# cubetto_1.net
KiCad netlist of a schematic drawn in EAGLE
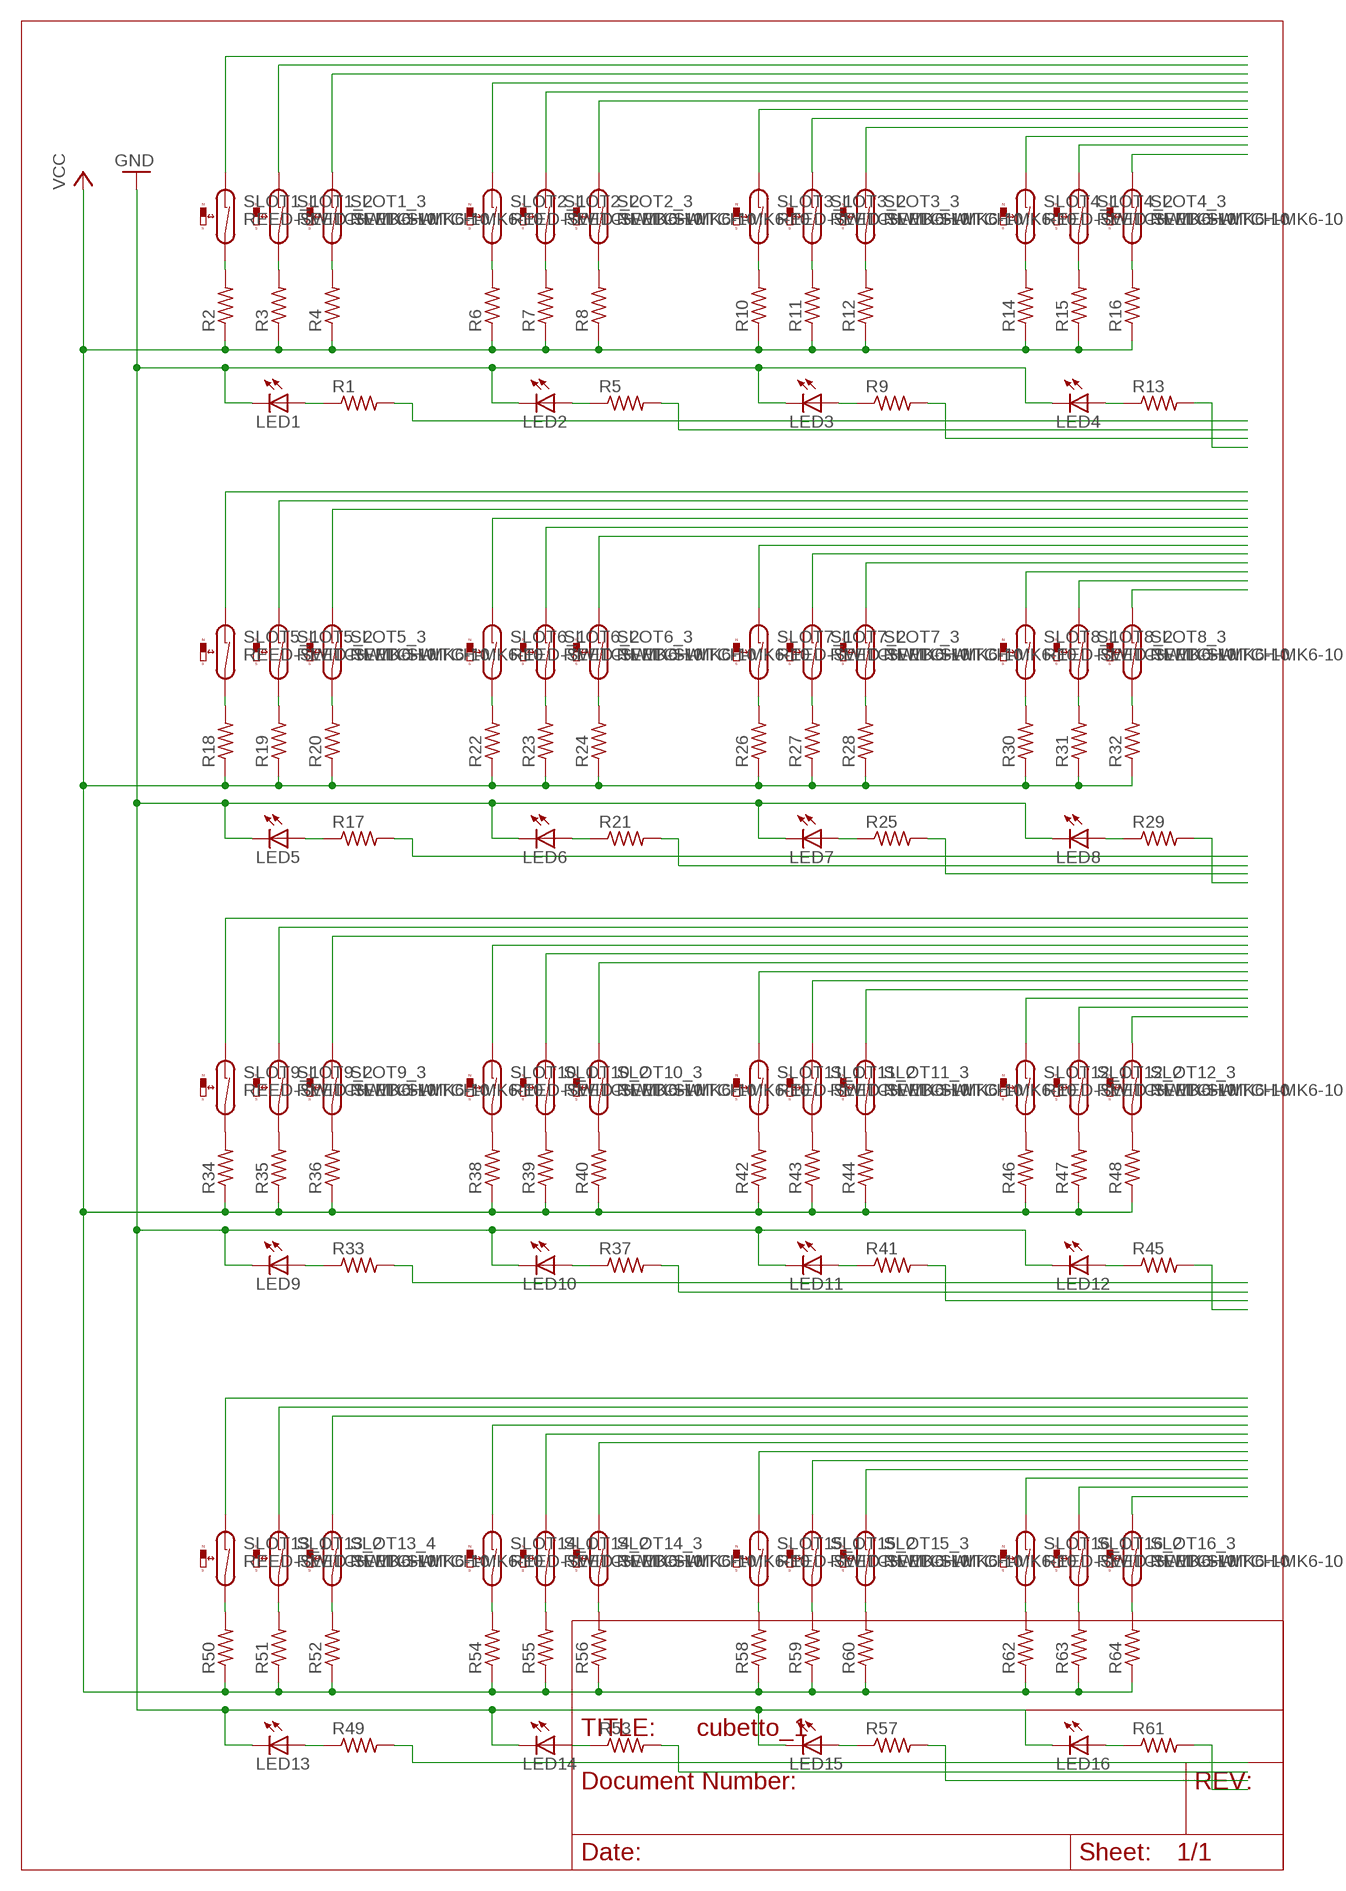
[diagram p0: schematic, sheet 1]

(export (version "E")
  (design (tool "Eeschema 10.0.6"))
  (components
    (comp (ref "LED1")
      (value "LED3MM")
      (footprint "eagle-import:LED3MM")
      (libsource (lib "eagle-import") (part "LED3MM"))
    )
    (comp (ref "LED2")
      (value "LED3MM")
      (footprint "eagle-import:LED3MM")
      (libsource (lib "eagle-import") (part "LED3MM"))
    )
    (comp (ref "LED3")
      (value "LED3MM")
      (footprint "eagle-import:LED3MM")
      (libsource (lib "eagle-import") (part "LED3MM"))
    )
    (comp (ref "LED4")
      (value "LED3MM")
      (footprint "eagle-import:LED3MM")
      (libsource (lib "eagle-import") (part "LED3MM"))
    )
    (comp (ref "LED5")
      (value "LED3MM")
      (footprint "eagle-import:LED3MM")
      (libsource (lib "eagle-import") (part "LED3MM"))
    )
    (comp (ref "LED6")
      (value "LED3MM")
      (footprint "eagle-import:LED3MM")
      (libsource (lib "eagle-import") (part "LED3MM"))
    )
    (comp (ref "LED7")
      (value "LED3MM")
      (footprint "eagle-import:LED3MM")
      (libsource (lib "eagle-import") (part "LED3MM"))
    )
    (comp (ref "LED8")
      (value "LED3MM")
      (footprint "eagle-import:LED3MM")
      (libsource (lib "eagle-import") (part "LED3MM"))
    )
    (comp (ref "LED9")
      (value "LED3MM")
      (footprint "eagle-import:LED3MM")
      (libsource (lib "eagle-import") (part "LED3MM"))
    )
    (comp (ref "LED10")
      (value "LED3MM")
      (footprint "eagle-import:LED3MM")
      (libsource (lib "eagle-import") (part "LED3MM"))
    )
    (comp (ref "LED11")
      (value "LED3MM")
      (footprint "eagle-import:LED3MM")
      (libsource (lib "eagle-import") (part "LED3MM"))
    )
    (comp (ref "LED12")
      (value "LED3MM")
      (footprint "eagle-import:LED3MM")
      (libsource (lib "eagle-import") (part "LED3MM"))
    )
    (comp (ref "LED13")
      (value "LED3MM")
      (footprint "eagle-import:LED3MM")
      (libsource (lib "eagle-import") (part "LED3MM"))
    )
    (comp (ref "LED14")
      (value "LED3MM")
      (footprint "eagle-import:LED3MM")
      (libsource (lib "eagle-import") (part "LED3MM"))
    )
    (comp (ref "LED15")
      (value "LED3MM")
      (footprint "eagle-import:LED3MM")
      (libsource (lib "eagle-import") (part "LED3MM"))
    )
    (comp (ref "LED16")
      (value "LED3MM")
      (footprint "eagle-import:LED3MM")
      (libsource (lib "eagle-import") (part "LED3MM"))
    )
    (comp (ref "R1")
      (value "R-US_0207/10")
      (footprint "eagle-import:0207_10")
      (libsource (lib "eagle-import") (part "R-US_0207/10"))
    )
    (comp (ref "R2")
      (value "R-US_0207/10")
      (footprint "eagle-import:0207_10")
      (libsource (lib "eagle-import") (part "R-US_0207/10"))
    )
    (comp (ref "R3")
      (value "R-US_0207/10")
      (footprint "eagle-import:0207_10")
      (libsource (lib "eagle-import") (part "R-US_0207/10"))
    )
    (comp (ref "R4")
      (value "R-US_0207/10")
      (footprint "eagle-import:0207_10")
      (libsource (lib "eagle-import") (part "R-US_0207/10"))
    )
    (comp (ref "R5")
      (value "R-US_0207/10")
      (footprint "eagle-import:0207_10")
      (libsource (lib "eagle-import") (part "R-US_0207/10"))
    )
    (comp (ref "R6")
      (value "R-US_0207/10")
      (footprint "eagle-import:0207_10")
      (libsource (lib "eagle-import") (part "R-US_0207/10"))
    )
    (comp (ref "R7")
      (value "R-US_0207/10")
      (footprint "eagle-import:0207_10")
      (libsource (lib "eagle-import") (part "R-US_0207/10"))
    )
    (comp (ref "R8")
      (value "R-US_0207/10")
      (footprint "eagle-import:0207_10")
      (libsource (lib "eagle-import") (part "R-US_0207/10"))
    )
    (comp (ref "R9")
      (value "R-US_0207/10")
      (footprint "eagle-import:0207_10")
      (libsource (lib "eagle-import") (part "R-US_0207/10"))
    )
    (comp (ref "R10")
      (value "R-US_0207/10")
      (footprint "eagle-import:0207_10")
      (libsource (lib "eagle-import") (part "R-US_0207/10"))
    )
    (comp (ref "R11")
      (value "R-US_0207/10")
      (footprint "eagle-import:0207_10")
      (libsource (lib "eagle-import") (part "R-US_0207/10"))
    )
    (comp (ref "R12")
      (value "R-US_0207/10")
      (footprint "eagle-import:0207_10")
      (libsource (lib "eagle-import") (part "R-US_0207/10"))
    )
    (comp (ref "R13")
      (value "R-US_0207/10")
      (footprint "eagle-import:0207_10")
      (libsource (lib "eagle-import") (part "R-US_0207/10"))
    )
    (comp (ref "R14")
      (value "R-US_0207/10")
      (footprint "eagle-import:0207_10")
      (libsource (lib "eagle-import") (part "R-US_0207/10"))
    )
    (comp (ref "R15")
      (value "R-US_0207/10")
      (footprint "eagle-import:0207_10")
      (libsource (lib "eagle-import") (part "R-US_0207/10"))
    )
    (comp (ref "R16")
      (value "R-US_0207/10")
      (footprint "eagle-import:0207_10")
      (libsource (lib "eagle-import") (part "R-US_0207/10"))
    )
    (comp (ref "R17")
      (value "R-US_0207/10")
      (footprint "eagle-import:0207_10")
      (libsource (lib "eagle-import") (part "R-US_0207/10"))
    )
    (comp (ref "R18")
      (value "R-US_0207/10")
      (footprint "eagle-import:0207_10")
      (libsource (lib "eagle-import") (part "R-US_0207/10"))
    )
    (comp (ref "R19")
      (value "R-US_0207/10")
      (footprint "eagle-import:0207_10")
      (libsource (lib "eagle-import") (part "R-US_0207/10"))
    )
    (comp (ref "R20")
      (value "R-US_0207/10")
      (footprint "eagle-import:0207_10")
      (libsource (lib "eagle-import") (part "R-US_0207/10"))
    )
    (comp (ref "R21")
      (value "R-US_0207/10")
      (footprint "eagle-import:0207_10")
      (libsource (lib "eagle-import") (part "R-US_0207/10"))
    )
    (comp (ref "R22")
      (value "R-US_0207/10")
      (footprint "eagle-import:0207_10")
      (libsource (lib "eagle-import") (part "R-US_0207/10"))
    )
    (comp (ref "R23")
      (value "R-US_0207/10")
      (footprint "eagle-import:0207_10")
      (libsource (lib "eagle-import") (part "R-US_0207/10"))
    )
    (comp (ref "R24")
      (value "R-US_0207/10")
      (footprint "eagle-import:0207_10")
      (libsource (lib "eagle-import") (part "R-US_0207/10"))
    )
    (comp (ref "R25")
      (value "R-US_0207/10")
      (footprint "eagle-import:0207_10")
      (libsource (lib "eagle-import") (part "R-US_0207/10"))
    )
    (comp (ref "R26")
      (value "R-US_0207/10")
      (footprint "eagle-import:0207_10")
      (libsource (lib "eagle-import") (part "R-US_0207/10"))
    )
    (comp (ref "R27")
      (value "R-US_0207/10")
      (footprint "eagle-import:0207_10")
      (libsource (lib "eagle-import") (part "R-US_0207/10"))
    )
    (comp (ref "R28")
      (value "R-US_0207/10")
      (footprint "eagle-import:0207_10")
      (libsource (lib "eagle-import") (part "R-US_0207/10"))
    )
    (comp (ref "R29")
      (value "R-US_0207/10")
      (footprint "eagle-import:0207_10")
      (libsource (lib "eagle-import") (part "R-US_0207/10"))
    )
    (comp (ref "R30")
      (value "R-US_0207/10")
      (footprint "eagle-import:0207_10")
      (libsource (lib "eagle-import") (part "R-US_0207/10"))
    )
    (comp (ref "R31")
      (value "R-US_0207/10")
      (footprint "eagle-import:0207_10")
      (libsource (lib "eagle-import") (part "R-US_0207/10"))
    )
    (comp (ref "R32")
      (value "R-US_0207/10")
      (footprint "eagle-import:0207_10")
      (libsource (lib "eagle-import") (part "R-US_0207/10"))
    )
    (comp (ref "R33")
      (value "R-US_0207/10")
      (footprint "eagle-import:0207_10")
      (libsource (lib "eagle-import") (part "R-US_0207/10"))
    )
    (comp (ref "R34")
      (value "R-US_0207/10")
      (footprint "eagle-import:0207_10")
      (libsource (lib "eagle-import") (part "R-US_0207/10"))
    )
    (comp (ref "R35")
      (value "R-US_0207/10")
      (footprint "eagle-import:0207_10")
      (libsource (lib "eagle-import") (part "R-US_0207/10"))
    )
    (comp (ref "R36")
      (value "R-US_0207/10")
      (footprint "eagle-import:0207_10")
      (libsource (lib "eagle-import") (part "R-US_0207/10"))
    )
    (comp (ref "R37")
      (value "R-US_0207/10")
      (footprint "eagle-import:0207_10")
      (libsource (lib "eagle-import") (part "R-US_0207/10"))
    )
    (comp (ref "R38")
      (value "R-US_0207/10")
      (footprint "eagle-import:0207_10")
      (libsource (lib "eagle-import") (part "R-US_0207/10"))
    )
    (comp (ref "R39")
      (value "R-US_0207/10")
      (footprint "eagle-import:0207_10")
      (libsource (lib "eagle-import") (part "R-US_0207/10"))
    )
    (comp (ref "R40")
      (value "R-US_0207/10")
      (footprint "eagle-import:0207_10")
      (libsource (lib "eagle-import") (part "R-US_0207/10"))
    )
    (comp (ref "R41")
      (value "R-US_0207/10")
      (footprint "eagle-import:0207_10")
      (libsource (lib "eagle-import") (part "R-US_0207/10"))
    )
    (comp (ref "R42")
      (value "R-US_0207/10")
      (footprint "eagle-import:0207_10")
      (libsource (lib "eagle-import") (part "R-US_0207/10"))
    )
    (comp (ref "R43")
      (value "R-US_0207/10")
      (footprint "eagle-import:0207_10")
      (libsource (lib "eagle-import") (part "R-US_0207/10"))
    )
    (comp (ref "R44")
      (value "R-US_0207/10")
      (footprint "eagle-import:0207_10")
      (libsource (lib "eagle-import") (part "R-US_0207/10"))
    )
    (comp (ref "R45")
      (value "R-US_0207/10")
      (footprint "eagle-import:0207_10")
      (libsource (lib "eagle-import") (part "R-US_0207/10"))
    )
    (comp (ref "R46")
      (value "R-US_0207/10")
      (footprint "eagle-import:0207_10")
      (libsource (lib "eagle-import") (part "R-US_0207/10"))
    )
    (comp (ref "R47")
      (value "R-US_0207/10")
      (footprint "eagle-import:0207_10")
      (libsource (lib "eagle-import") (part "R-US_0207/10"))
    )
    (comp (ref "R48")
      (value "R-US_0207/10")
      (footprint "eagle-import:0207_10")
      (libsource (lib "eagle-import") (part "R-US_0207/10"))
    )
    (comp (ref "R49")
      (value "R-US_0207/10")
      (footprint "eagle-import:0207_10")
      (libsource (lib "eagle-import") (part "R-US_0207/10"))
    )
    (comp (ref "R50")
      (value "R-US_0207/10")
      (footprint "eagle-import:0207_10")
      (libsource (lib "eagle-import") (part "R-US_0207/10"))
    )
    (comp (ref "R51")
      (value "R-US_0207/10")
      (footprint "eagle-import:0207_10")
      (libsource (lib "eagle-import") (part "R-US_0207/10"))
    )
    (comp (ref "R52")
      (value "R-US_0207/10")
      (footprint "eagle-import:0207_10")
      (libsource (lib "eagle-import") (part "R-US_0207/10"))
    )
    (comp (ref "R53")
      (value "R-US_0207/10")
      (footprint "eagle-import:0207_10")
      (libsource (lib "eagle-import") (part "R-US_0207/10"))
    )
    (comp (ref "R54")
      (value "R-US_0207/10")
      (footprint "eagle-import:0207_10")
      (libsource (lib "eagle-import") (part "R-US_0207/10"))
    )
    (comp (ref "R55")
      (value "R-US_0207/10")
      (footprint "eagle-import:0207_10")
      (libsource (lib "eagle-import") (part "R-US_0207/10"))
    )
    (comp (ref "R56")
      (value "R-US_0207/10")
      (footprint "eagle-import:0207_10")
      (libsource (lib "eagle-import") (part "R-US_0207/10"))
    )
    (comp (ref "R57")
      (value "R-US_0207/10")
      (footprint "eagle-import:0207_10")
      (libsource (lib "eagle-import") (part "R-US_0207/10"))
    )
    (comp (ref "R58")
      (value "R-US_0207/10")
      (footprint "eagle-import:0207_10")
      (libsource (lib "eagle-import") (part "R-US_0207/10"))
    )
    (comp (ref "R59")
      (value "R-US_0207/10")
      (footprint "eagle-import:0207_10")
      (libsource (lib "eagle-import") (part "R-US_0207/10"))
    )
    (comp (ref "R60")
      (value "R-US_0207/10")
      (footprint "eagle-import:0207_10")
      (libsource (lib "eagle-import") (part "R-US_0207/10"))
    )
    (comp (ref "R61")
      (value "R-US_0207/10")
      (footprint "eagle-import:0207_10")
      (libsource (lib "eagle-import") (part "R-US_0207/10"))
    )
    (comp (ref "R62")
      (value "R-US_0207/10")
      (footprint "eagle-import:0207_10")
      (libsource (lib "eagle-import") (part "R-US_0207/10"))
    )
    (comp (ref "R63")
      (value "R-US_0207/10")
      (footprint "eagle-import:0207_10")
      (libsource (lib "eagle-import") (part "R-US_0207/10"))
    )
    (comp (ref "R64")
      (value "R-US_0207/10")
      (footprint "eagle-import:0207_10")
      (libsource (lib "eagle-import") (part "R-US_0207/10"))
    )
    (comp (ref "SLOT1_1")
      (value "REED-SWITCH-MK6-10")
      (footprint "eagle-import:MK6-10")
      (libsource (lib "eagle-import") (part "REED-SWITCH-MK6-10"))
    )
    (comp (ref "SLOT1_2")
      (value "REED-SWITCH-MK6-10")
      (footprint "eagle-import:MK6-10")
      (libsource (lib "eagle-import") (part "REED-SWITCH-MK6-10"))
    )
    (comp (ref "SLOT1_3")
      (value "REED-SWITCH-MK6-10")
      (footprint "eagle-import:MK6-10")
      (libsource (lib "eagle-import") (part "REED-SWITCH-MK6-10"))
    )
    (comp (ref "SLOT2_1")
      (value "REED-SWITCH-MK6-10")
      (footprint "eagle-import:MK6-10")
      (libsource (lib "eagle-import") (part "REED-SWITCH-MK6-10"))
    )
    (comp (ref "SLOT2_2")
      (value "REED-SWITCH-MK6-10")
      (footprint "eagle-import:MK6-10")
      (libsource (lib "eagle-import") (part "REED-SWITCH-MK6-10"))
    )
    (comp (ref "SLOT2_3")
      (value "REED-SWITCH-MK6-10")
      (footprint "eagle-import:MK6-10")
      (libsource (lib "eagle-import") (part "REED-SWITCH-MK6-10"))
    )
    (comp (ref "SLOT3_1")
      (value "REED-SWITCH-MK6-10")
      (footprint "eagle-import:MK6-10")
      (libsource (lib "eagle-import") (part "REED-SWITCH-MK6-10"))
    )
    (comp (ref "SLOT3_2")
      (value "REED-SWITCH-MK6-10")
      (footprint "eagle-import:MK6-10")
      (libsource (lib "eagle-import") (part "REED-SWITCH-MK6-10"))
    )
    (comp (ref "SLOT3_3")
      (value "REED-SWITCH-MK6-10")
      (footprint "eagle-import:MK6-10")
      (libsource (lib "eagle-import") (part "REED-SWITCH-MK6-10"))
    )
    (comp (ref "SLOT4_1")
      (value "REED-SWITCH-MK6-10")
      (footprint "eagle-import:MK6-10")
      (libsource (lib "eagle-import") (part "REED-SWITCH-MK6-10"))
    )
    (comp (ref "SLOT4_2")
      (value "REED-SWITCH-MK6-10")
      (footprint "eagle-import:MK6-10")
      (libsource (lib "eagle-import") (part "REED-SWITCH-MK6-10"))
    )
    (comp (ref "SLOT4_3")
      (value "REED-SWITCH-MK6-10")
      (footprint "eagle-import:MK6-10")
      (libsource (lib "eagle-import") (part "REED-SWITCH-MK6-10"))
    )
    (comp (ref "SLOT5_1")
      (value "REED-SWITCH-MK6-10")
      (footprint "eagle-import:MK6-10")
      (libsource (lib "eagle-import") (part "REED-SWITCH-MK6-10"))
    )
    (comp (ref "SLOT5_2")
      (value "REED-SWITCH-MK6-10")
      (footprint "eagle-import:MK6-10")
      (libsource (lib "eagle-import") (part "REED-SWITCH-MK6-10"))
    )
    (comp (ref "SLOT5_3")
      (value "REED-SWITCH-MK6-10")
      (footprint "eagle-import:MK6-10")
      (libsource (lib "eagle-import") (part "REED-SWITCH-MK6-10"))
    )
    (comp (ref "SLOT6_1")
      (value "REED-SWITCH-MK6-10")
      (footprint "eagle-import:MK6-10")
      (libsource (lib "eagle-import") (part "REED-SWITCH-MK6-10"))
    )
    (comp (ref "SLOT6_2")
      (value "REED-SWITCH-MK6-10")
      (footprint "eagle-import:MK6-10")
      (libsource (lib "eagle-import") (part "REED-SWITCH-MK6-10"))
    )
    (comp (ref "SLOT6_3")
      (value "REED-SWITCH-MK6-10")
      (footprint "eagle-import:MK6-10")
      (libsource (lib "eagle-import") (part "REED-SWITCH-MK6-10"))
    )
    (comp (ref "SLOT7_1")
      (value "REED-SWITCH-MK6-10")
      (footprint "eagle-import:MK6-10")
      (libsource (lib "eagle-import") (part "REED-SWITCH-MK6-10"))
    )
    (comp (ref "SLOT7_2")
      (value "REED-SWITCH-MK6-10")
      (footprint "eagle-import:MK6-10")
      (libsource (lib "eagle-import") (part "REED-SWITCH-MK6-10"))
    )
    (comp (ref "SLOT7_3")
      (value "REED-SWITCH-MK6-10")
      (footprint "eagle-import:MK6-10")
      (libsource (lib "eagle-import") (part "REED-SWITCH-MK6-10"))
    )
    (comp (ref "SLOT8_1")
      (value "REED-SWITCH-MK6-10")
      (footprint "eagle-import:MK6-10")
      (libsource (lib "eagle-import") (part "REED-SWITCH-MK6-10"))
    )
    (comp (ref "SLOT8_2")
      (value "REED-SWITCH-MK6-10")
      (footprint "eagle-import:MK6-10")
      (libsource (lib "eagle-import") (part "REED-SWITCH-MK6-10"))
    )
    (comp (ref "SLOT8_3")
      (value "REED-SWITCH-MK6-10")
      (footprint "eagle-import:MK6-10")
      (libsource (lib "eagle-import") (part "REED-SWITCH-MK6-10"))
    )
    (comp (ref "SLOT9_1")
      (value "REED-SWITCH-MK6-10")
      (footprint "eagle-import:MK6-10")
      (libsource (lib "eagle-import") (part "REED-SWITCH-MK6-10"))
    )
    (comp (ref "SLOT9_2")
      (value "REED-SWITCH-MK6-10")
      (footprint "eagle-import:MK6-10")
      (libsource (lib "eagle-import") (part "REED-SWITCH-MK6-10"))
    )
    (comp (ref "SLOT9_3")
      (value "REED-SWITCH-MK6-10")
      (footprint "eagle-import:MK6-10")
      (libsource (lib "eagle-import") (part "REED-SWITCH-MK6-10"))
    )
    (comp (ref "SLOT10_1")
      (value "REED-SWITCH-MK6-10")
      (footprint "eagle-import:MK6-10")
      (libsource (lib "eagle-import") (part "REED-SWITCH-MK6-10"))
    )
    (comp (ref "SLOT10_2")
      (value "REED-SWITCH-MK6-10")
      (footprint "eagle-import:MK6-10")
      (libsource (lib "eagle-import") (part "REED-SWITCH-MK6-10"))
    )
    (comp (ref "SLOT10_3")
      (value "REED-SWITCH-MK6-10")
      (footprint "eagle-import:MK6-10")
      (libsource (lib "eagle-import") (part "REED-SWITCH-MK6-10"))
    )
    (comp (ref "SLOT11_1")
      (value "REED-SWITCH-MK6-10")
      (footprint "eagle-import:MK6-10")
      (libsource (lib "eagle-import") (part "REED-SWITCH-MK6-10"))
    )
    (comp (ref "SLOT11_2")
      (value "REED-SWITCH-MK6-10")
      (footprint "eagle-import:MK6-10")
      (libsource (lib "eagle-import") (part "REED-SWITCH-MK6-10"))
    )
    (comp (ref "SLOT11_3")
      (value "REED-SWITCH-MK6-10")
      (footprint "eagle-import:MK6-10")
      (libsource (lib "eagle-import") (part "REED-SWITCH-MK6-10"))
    )
    (comp (ref "SLOT12_1")
      (value "REED-SWITCH-MK6-10")
      (footprint "eagle-import:MK6-10")
      (libsource (lib "eagle-import") (part "REED-SWITCH-MK6-10"))
    )
    (comp (ref "SLOT12_2")
      (value "REED-SWITCH-MK6-10")
      (footprint "eagle-import:MK6-10")
      (libsource (lib "eagle-import") (part "REED-SWITCH-MK6-10"))
    )
    (comp (ref "SLOT12_3")
      (value "REED-SWITCH-MK6-10")
      (footprint "eagle-import:MK6-10")
      (libsource (lib "eagle-import") (part "REED-SWITCH-MK6-10"))
    )
    (comp (ref "SLOT13_1")
      (value "REED-SWITCH-MK6-10")
      (footprint "eagle-import:MK6-10")
      (libsource (lib "eagle-import") (part "REED-SWITCH-MK6-10"))
    )
    (comp (ref "SLOT13_2")
      (value "REED-SWITCH-MK6-10")
      (footprint "eagle-import:MK6-10")
      (libsource (lib "eagle-import") (part "REED-SWITCH-MK6-10"))
    )
    (comp (ref "SLOT13_4")
      (value "REED-SWITCH-MK6-10")
      (footprint "eagle-import:MK6-10")
      (libsource (lib "eagle-import") (part "REED-SWITCH-MK6-10"))
    )
    (comp (ref "SLOT14_1")
      (value "REED-SWITCH-MK6-10")
      (footprint "eagle-import:MK6-10")
      (libsource (lib "eagle-import") (part "REED-SWITCH-MK6-10"))
    )
    (comp (ref "SLOT14_2")
      (value "REED-SWITCH-MK6-10")
      (footprint "eagle-import:MK6-10")
      (libsource (lib "eagle-import") (part "REED-SWITCH-MK6-10"))
    )
    (comp (ref "SLOT14_3")
      (value "REED-SWITCH-MK6-10")
      (footprint "eagle-import:MK6-10")
      (libsource (lib "eagle-import") (part "REED-SWITCH-MK6-10"))
    )
    (comp (ref "SLOT15_1")
      (value "REED-SWITCH-MK6-10")
      (footprint "eagle-import:MK6-10")
      (libsource (lib "eagle-import") (part "REED-SWITCH-MK6-10"))
    )
    (comp (ref "SLOT15_2")
      (value "REED-SWITCH-MK6-10")
      (footprint "eagle-import:MK6-10")
      (libsource (lib "eagle-import") (part "REED-SWITCH-MK6-10"))
    )
    (comp (ref "SLOT15_3")
      (value "REED-SWITCH-MK6-10")
      (footprint "eagle-import:MK6-10")
      (libsource (lib "eagle-import") (part "REED-SWITCH-MK6-10"))
    )
    (comp (ref "SLOT16_1")
      (value "REED-SWITCH-MK6-10")
      (footprint "eagle-import:MK6-10")
      (libsource (lib "eagle-import") (part "REED-SWITCH-MK6-10"))
    )
    (comp (ref "SLOT16_2")
      (value "REED-SWITCH-MK6-10")
      (footprint "eagle-import:MK6-10")
      (libsource (lib "eagle-import") (part "REED-SWITCH-MK6-10"))
    )
    (comp (ref "SLOT16_3")
      (value "REED-SWITCH-MK6-10")
      (footprint "eagle-import:MK6-10")
      (libsource (lib "eagle-import") (part "REED-SWITCH-MK6-10"))
    )
  )
  (nets
    (net (code "1") (name "GND") (class "Default")
      (node (ref "LED1") (pin "K") (pinfunction "C_K") (pintype "passive"))
      (node (ref "LED10") (pin "K") (pinfunction "C_K") (pintype "passive"))
      (node (ref "LED11") (pin "K") (pinfunction "C_K") (pintype "passive"))
      (node (ref "LED12") (pin "K") (pinfunction "C_K") (pintype "passive"))
      (node (ref "LED13") (pin "K") (pinfunction "C_K") (pintype "passive"))
      (node (ref "LED14") (pin "K") (pinfunction "C_K") (pintype "passive"))
      (node (ref "LED15") (pin "K") (pinfunction "C_K") (pintype "passive"))
      (node (ref "LED16") (pin "K") (pinfunction "C_K") (pintype "passive"))
      (node (ref "LED2") (pin "K") (pinfunction "C_K") (pintype "passive"))
      (node (ref "LED3") (pin "K") (pinfunction "C_K") (pintype "passive"))
      (node (ref "LED4") (pin "K") (pinfunction "C_K") (pintype "passive"))
      (node (ref "LED5") (pin "K") (pinfunction "C_K") (pintype "passive"))
      (node (ref "LED6") (pin "K") (pinfunction "C_K") (pintype "passive"))
      (node (ref "LED7") (pin "K") (pinfunction "C_K") (pintype "passive"))
      (node (ref "LED8") (pin "K") (pinfunction "C_K") (pintype "passive"))
      (node (ref "LED9") (pin "K") (pinfunction "C_K") (pintype "passive"))
    )
    (net (code "2") (name "Net-(LED1-PadA)") (class "Default")
      (node (ref "LED1") (pin "A") (pinfunction "A_A") (pintype "passive"))
      (node (ref "R1") (pin "1") (pinfunction "1_1") (pintype "passive"))
    )
    (net (code "3") (name "Net-(LED2-PadA)") (class "Default")
      (node (ref "LED2") (pin "A") (pinfunction "A_A") (pintype "passive"))
      (node (ref "R5") (pin "1") (pinfunction "1_1") (pintype "passive"))
    )
    (net (code "4") (name "Net-(LED3-PadA)") (class "Default")
      (node (ref "LED3") (pin "A") (pinfunction "A_A") (pintype "passive"))
      (node (ref "R9") (pin "1") (pinfunction "1_1") (pintype "passive"))
    )
    (net (code "5") (name "Net-(LED4-PadA)") (class "Default")
      (node (ref "LED4") (pin "A") (pinfunction "A_A") (pintype "passive"))
      (node (ref "R13") (pin "1") (pinfunction "1_1") (pintype "passive"))
    )
    (net (code "6") (name "Net-(LED5-PadA)") (class "Default")
      (node (ref "LED5") (pin "A") (pinfunction "A_A") (pintype "passive"))
      (node (ref "R17") (pin "1") (pinfunction "1_1") (pintype "passive"))
    )
    (net (code "7") (name "Net-(LED6-PadA)") (class "Default")
      (node (ref "LED6") (pin "A") (pinfunction "A_A") (pintype "passive"))
      (node (ref "R21") (pin "1") (pinfunction "1_1") (pintype "passive"))
    )
    (net (code "8") (name "Net-(LED7-PadA)") (class "Default")
      (node (ref "LED7") (pin "A") (pinfunction "A_A") (pintype "passive"))
      (node (ref "R25") (pin "1") (pinfunction "1_1") (pintype "passive"))
    )
    (net (code "9") (name "Net-(LED8-PadA)") (class "Default")
      (node (ref "LED8") (pin "A") (pinfunction "A_A") (pintype "passive"))
      (node (ref "R29") (pin "1") (pinfunction "1_1") (pintype "passive"))
    )
    (net (code "10") (name "Net-(LED9-PadA)") (class "Default")
      (node (ref "LED9") (pin "A") (pinfunction "A_A") (pintype "passive"))
      (node (ref "R33") (pin "1") (pinfunction "1_1") (pintype "passive"))
    )
    (net (code "11") (name "Net-(LED10-PadA)") (class "Default")
      (node (ref "LED10") (pin "A") (pinfunction "A_A") (pintype "passive"))
      (node (ref "R37") (pin "1") (pinfunction "1_1") (pintype "passive"))
    )
    (net (code "12") (name "Net-(LED11-PadA)") (class "Default")
      (node (ref "LED11") (pin "A") (pinfunction "A_A") (pintype "passive"))
      (node (ref "R41") (pin "1") (pinfunction "1_1") (pintype "passive"))
    )
    (net (code "13") (name "Net-(LED12-PadA)") (class "Default")
      (node (ref "LED12") (pin "A") (pinfunction "A_A") (pintype "passive"))
      (node (ref "R45") (pin "1") (pinfunction "1_1") (pintype "passive"))
    )
    (net (code "14") (name "Net-(LED13-PadA)") (class "Default")
      (node (ref "LED13") (pin "A") (pinfunction "A_A") (pintype "passive"))
      (node (ref "R49") (pin "1") (pinfunction "1_1") (pintype "passive"))
    )
    (net (code "15") (name "Net-(LED14-PadA)") (class "Default")
      (node (ref "LED14") (pin "A") (pinfunction "A_A") (pintype "passive"))
      (node (ref "R53") (pin "1") (pinfunction "1_1") (pintype "passive"))
    )
    (net (code "16") (name "Net-(LED15-PadA)") (class "Default")
      (node (ref "LED15") (pin "A") (pinfunction "A_A") (pintype "passive"))
      (node (ref "R57") (pin "1") (pinfunction "1_1") (pintype "passive"))
    )
    (net (code "17") (name "Net-(LED16-PadA)") (class "Default")
      (node (ref "LED16") (pin "A") (pinfunction "A_A") (pintype "passive"))
      (node (ref "R61") (pin "1") (pinfunction "1_1") (pintype "passive"))
    )
    (net (code "18") (name "Net-(R2-Pad2)") (class "Default")
      (node (ref "R2") (pin "2") (pinfunction "2_2") (pintype "passive"))
      (node (ref "SLOT1_1") (pin "2") (pinfunction "2_2") (pintype "passive"))
    )
    (net (code "19") (name "Net-(R3-Pad2)") (class "Default")
      (node (ref "R3") (pin "2") (pinfunction "2_2") (pintype "passive"))
      (node (ref "SLOT1_2") (pin "2") (pinfunction "2_2") (pintype "passive"))
    )
    (net (code "20") (name "Net-(R4-Pad2)") (class "Default")
      (node (ref "R4") (pin "2") (pinfunction "2_2") (pintype "passive"))
      (node (ref "SLOT1_3") (pin "2") (pinfunction "2_2") (pintype "passive"))
    )
    (net (code "21") (name "Net-(R6-Pad2)") (class "Default")
      (node (ref "R6") (pin "2") (pinfunction "2_2") (pintype "passive"))
      (node (ref "SLOT2_1") (pin "2") (pinfunction "2_2") (pintype "passive"))
    )
    (net (code "22") (name "Net-(R7-Pad2)") (class "Default")
      (node (ref "R7") (pin "2") (pinfunction "2_2") (pintype "passive"))
      (node (ref "SLOT2_2") (pin "2") (pinfunction "2_2") (pintype "passive"))
    )
    (net (code "23") (name "Net-(R8-Pad2)") (class "Default")
      (node (ref "R8") (pin "2") (pinfunction "2_2") (pintype "passive"))
      (node (ref "SLOT2_3") (pin "2") (pinfunction "2_2") (pintype "passive"))
    )
    (net (code "24") (name "Net-(R10-Pad2)") (class "Default")
      (node (ref "R10") (pin "2") (pinfunction "2_2") (pintype "passive"))
      (node (ref "SLOT3_1") (pin "2") (pinfunction "2_2") (pintype "passive"))
    )
    (net (code "25") (name "Net-(R11-Pad2)") (class "Default")
      (node (ref "R11") (pin "2") (pinfunction "2_2") (pintype "passive"))
      (node (ref "SLOT3_2") (pin "2") (pinfunction "2_2") (pintype "passive"))
    )
    (net (code "26") (name "Net-(R12-Pad2)") (class "Default")
      (node (ref "R12") (pin "2") (pinfunction "2_2") (pintype "passive"))
      (node (ref "SLOT3_3") (pin "2") (pinfunction "2_2") (pintype "passive"))
    )
    (net (code "27") (name "Net-(R14-Pad2)") (class "Default")
      (node (ref "R14") (pin "2") (pinfunction "2_2") (pintype "passive"))
      (node (ref "SLOT4_1") (pin "2") (pinfunction "2_2") (pintype "passive"))
    )
    (net (code "28") (name "Net-(R15-Pad2)") (class "Default")
      (node (ref "R15") (pin "2") (pinfunction "2_2") (pintype "passive"))
      (node (ref "SLOT4_2") (pin "2") (pinfunction "2_2") (pintype "passive"))
    )
    (net (code "29") (name "Net-(R16-Pad2)") (class "Default")
      (node (ref "R16") (pin "2") (pinfunction "2_2") (pintype "passive"))
      (node (ref "SLOT4_3") (pin "2") (pinfunction "2_2") (pintype "passive"))
    )
    (net (code "30") (name "Net-(R18-Pad2)") (class "Default")
      (node (ref "R18") (pin "2") (pinfunction "2_2") (pintype "passive"))
      (node (ref "SLOT5_1") (pin "2") (pinfunction "2_2") (pintype "passive"))
    )
    (net (code "31") (name "Net-(R19-Pad2)") (class "Default")
      (node (ref "R19") (pin "2") (pinfunction "2_2") (pintype "passive"))
      (node (ref "SLOT5_2") (pin "2") (pinfunction "2_2") (pintype "passive"))
    )
    (net (code "32") (name "Net-(R20-Pad2)") (class "Default")
      (node (ref "R20") (pin "2") (pinfunction "2_2") (pintype "passive"))
      (node (ref "SLOT5_3") (pin "2") (pinfunction "2_2") (pintype "passive"))
    )
    (net (code "33") (name "Net-(R22-Pad2)") (class "Default")
      (node (ref "R22") (pin "2") (pinfunction "2_2") (pintype "passive"))
      (node (ref "SLOT6_1") (pin "2") (pinfunction "2_2") (pintype "passive"))
    )
    (net (code "34") (name "Net-(R23-Pad2)") (class "Default")
      (node (ref "R23") (pin "2") (pinfunction "2_2") (pintype "passive"))
      (node (ref "SLOT6_2") (pin "2") (pinfunction "2_2") (pintype "passive"))
    )
    (net (code "35") (name "Net-(R24-Pad2)") (class "Default")
      (node (ref "R24") (pin "2") (pinfunction "2_2") (pintype "passive"))
      (node (ref "SLOT6_3") (pin "2") (pinfunction "2_2") (pintype "passive"))
    )
    (net (code "36") (name "Net-(R26-Pad2)") (class "Default")
      (node (ref "R26") (pin "2") (pinfunction "2_2") (pintype "passive"))
      (node (ref "SLOT7_1") (pin "2") (pinfunction "2_2") (pintype "passive"))
    )
    (net (code "37") (name "Net-(R27-Pad2)") (class "Default")
      (node (ref "R27") (pin "2") (pinfunction "2_2") (pintype "passive"))
      (node (ref "SLOT7_2") (pin "2") (pinfunction "2_2") (pintype "passive"))
    )
    (net (code "38") (name "Net-(R28-Pad2)") (class "Default")
      (node (ref "R28") (pin "2") (pinfunction "2_2") (pintype "passive"))
      (node (ref "SLOT7_3") (pin "2") (pinfunction "2_2") (pintype "passive"))
    )
    (net (code "39") (name "Net-(R30-Pad2)") (class "Default")
      (node (ref "R30") (pin "2") (pinfunction "2_2") (pintype "passive"))
      (node (ref "SLOT8_1") (pin "2") (pinfunction "2_2") (pintype "passive"))
    )
    (net (code "40") (name "Net-(R31-Pad2)") (class "Default")
      (node (ref "R31") (pin "2") (pinfunction "2_2") (pintype "passive"))
      (node (ref "SLOT8_2") (pin "2") (pinfunction "2_2") (pintype "passive"))
    )
    (net (code "41") (name "Net-(R32-Pad2)") (class "Default")
      (node (ref "R32") (pin "2") (pinfunction "2_2") (pintype "passive"))
      (node (ref "SLOT8_3") (pin "2") (pinfunction "2_2") (pintype "passive"))
    )
    (net (code "42") (name "Net-(R34-Pad2)") (class "Default")
      (node (ref "R34") (pin "2") (pinfunction "2_2") (pintype "passive"))
      (node (ref "SLOT9_1") (pin "2") (pinfunction "2_2") (pintype "passive"))
    )
    (net (code "43") (name "Net-(R35-Pad2)") (class "Default")
      (node (ref "R35") (pin "2") (pinfunction "2_2") (pintype "passive"))
      (node (ref "SLOT9_2") (pin "2") (pinfunction "2_2") (pintype "passive"))
    )
    (net (code "44") (name "Net-(R36-Pad2)") (class "Default")
      (node (ref "R36") (pin "2") (pinfunction "2_2") (pintype "passive"))
      (node (ref "SLOT9_3") (pin "2") (pinfunction "2_2") (pintype "passive"))
    )
    (net (code "45") (name "Net-(R38-Pad2)") (class "Default")
      (node (ref "R38") (pin "2") (pinfunction "2_2") (pintype "passive"))
      (node (ref "SLOT10_1") (pin "2") (pinfunction "2_2") (pintype "passive"))
    )
    (net (code "46") (name "Net-(R39-Pad2)") (class "Default")
      (node (ref "R39") (pin "2") (pinfunction "2_2") (pintype "passive"))
      (node (ref "SLOT10_2") (pin "2") (pinfunction "2_2") (pintype "passive"))
    )
    (net (code "47") (name "Net-(R40-Pad2)") (class "Default")
      (node (ref "R40") (pin "2") (pinfunction "2_2") (pintype "passive"))
      (node (ref "SLOT10_3") (pin "2") (pinfunction "2_2") (pintype "passive"))
    )
    (net (code "48") (name "Net-(R42-Pad2)") (class "Default")
      (node (ref "R42") (pin "2") (pinfunction "2_2") (pintype "passive"))
      (node (ref "SLOT11_1") (pin "2") (pinfunction "2_2") (pintype "passive"))
    )
    (net (code "49") (name "Net-(R43-Pad2)") (class "Default")
      (node (ref "R43") (pin "2") (pinfunction "2_2") (pintype "passive"))
      (node (ref "SLOT11_2") (pin "2") (pinfunction "2_2") (pintype "passive"))
    )
    (net (code "50") (name "Net-(R44-Pad2)") (class "Default")
      (node (ref "R44") (pin "2") (pinfunction "2_2") (pintype "passive"))
      (node (ref "SLOT11_3") (pin "2") (pinfunction "2_2") (pintype "passive"))
    )
    (net (code "51") (name "Net-(R46-Pad2)") (class "Default")
      (node (ref "R46") (pin "2") (pinfunction "2_2") (pintype "passive"))
      (node (ref "SLOT12_1") (pin "2") (pinfunction "2_2") (pintype "passive"))
    )
    (net (code "52") (name "Net-(R47-Pad2)") (class "Default")
      (node (ref "R47") (pin "2") (pinfunction "2_2") (pintype "passive"))
      (node (ref "SLOT12_2") (pin "2") (pinfunction "2_2") (pintype "passive"))
    )
    (net (code "53") (name "Net-(R48-Pad2)") (class "Default")
      (node (ref "R48") (pin "2") (pinfunction "2_2") (pintype "passive"))
      (node (ref "SLOT12_3") (pin "2") (pinfunction "2_2") (pintype "passive"))
    )
    (net (code "54") (name "Net-(R50-Pad2)") (class "Default")
      (node (ref "R50") (pin "2") (pinfunction "2_2") (pintype "passive"))
      (node (ref "SLOT13_1") (pin "2") (pinfunction "2_2") (pintype "passive"))
    )
    (net (code "55") (name "Net-(R51-Pad2)") (class "Default")
      (node (ref "R51") (pin "2") (pinfunction "2_2") (pintype "passive"))
      (node (ref "SLOT13_2") (pin "2") (pinfunction "2_2") (pintype "passive"))
    )
    (net (code "56") (name "Net-(R52-Pad2)") (class "Default")
      (node (ref "R52") (pin "2") (pinfunction "2_2") (pintype "passive"))
      (node (ref "SLOT13_4") (pin "2") (pinfunction "2_2") (pintype "passive"))
    )
    (net (code "57") (name "Net-(R54-Pad2)") (class "Default")
      (node (ref "R54") (pin "2") (pinfunction "2_2") (pintype "passive"))
      (node (ref "SLOT14_1") (pin "2") (pinfunction "2_2") (pintype "passive"))
    )
    (net (code "58") (name "Net-(R55-Pad2)") (class "Default")
      (node (ref "R55") (pin "2") (pinfunction "2_2") (pintype "passive"))
      (node (ref "SLOT14_2") (pin "2") (pinfunction "2_2") (pintype "passive"))
    )
    (net (code "59") (name "Net-(R56-Pad2)") (class "Default")
      (node (ref "R56") (pin "2") (pinfunction "2_2") (pintype "passive"))
      (node (ref "SLOT14_3") (pin "2") (pinfunction "2_2") (pintype "passive"))
    )
    (net (code "60") (name "Net-(R58-Pad2)") (class "Default")
      (node (ref "R58") (pin "2") (pinfunction "2_2") (pintype "passive"))
      (node (ref "SLOT15_1") (pin "2") (pinfunction "2_2") (pintype "passive"))
    )
    (net (code "61") (name "Net-(R59-Pad2)") (class "Default")
      (node (ref "R59") (pin "2") (pinfunction "2_2") (pintype "passive"))
      (node (ref "SLOT15_2") (pin "2") (pinfunction "2_2") (pintype "passive"))
    )
    (net (code "62") (name "Net-(R60-Pad2)") (class "Default")
      (node (ref "R60") (pin "2") (pinfunction "2_2") (pintype "passive"))
      (node (ref "SLOT15_3") (pin "2") (pinfunction "2_2") (pintype "passive"))
    )
    (net (code "63") (name "Net-(R62-Pad2)") (class "Default")
      (node (ref "R62") (pin "2") (pinfunction "2_2") (pintype "passive"))
      (node (ref "SLOT16_1") (pin "2") (pinfunction "2_2") (pintype "passive"))
    )
    (net (code "64") (name "Net-(R63-Pad2)") (class "Default")
      (node (ref "R63") (pin "2") (pinfunction "2_2") (pintype "passive"))
      (node (ref "SLOT16_2") (pin "2") (pinfunction "2_2") (pintype "passive"))
    )
    (net (code "65") (name "Net-(R64-Pad2)") (class "Default")
      (node (ref "R64") (pin "2") (pinfunction "2_2") (pintype "passive"))
      (node (ref "SLOT16_3") (pin "2") (pinfunction "2_2") (pintype "passive"))
    )
    (net (code "66") (name "VCC") (class "Default")
      (node (ref "R10") (pin "1") (pinfunction "1_1") (pintype "passive"))
      (node (ref "R11") (pin "1") (pinfunction "1_1") (pintype "passive"))
      (node (ref "R12") (pin "1") (pinfunction "1_1") (pintype "passive"))
      (node (ref "R14") (pin "1") (pinfunction "1_1") (pintype "passive"))
      (node (ref "R15") (pin "1") (pinfunction "1_1") (pintype "passive"))
      (node (ref "R16") (pin "1") (pinfunction "1_1") (pintype "passive"))
      (node (ref "R18") (pin "1") (pinfunction "1_1") (pintype "passive"))
      (node (ref "R19") (pin "1") (pinfunction "1_1") (pintype "passive"))
      (node (ref "R2") (pin "1") (pinfunction "1_1") (pintype "passive"))
      (node (ref "R20") (pin "1") (pinfunction "1_1") (pintype "passive"))
      (node (ref "R22") (pin "1") (pinfunction "1_1") (pintype "passive"))
      (node (ref "R23") (pin "1") (pinfunction "1_1") (pintype "passive"))
      (node (ref "R24") (pin "1") (pinfunction "1_1") (pintype "passive"))
      (node (ref "R26") (pin "1") (pinfunction "1_1") (pintype "passive"))
      (node (ref "R27") (pin "1") (pinfunction "1_1") (pintype "passive"))
      (node (ref "R28") (pin "1") (pinfunction "1_1") (pintype "passive"))
      (node (ref "R3") (pin "1") (pinfunction "1_1") (pintype "passive"))
      (node (ref "R30") (pin "1") (pinfunction "1_1") (pintype "passive"))
      (node (ref "R31") (pin "1") (pinfunction "1_1") (pintype "passive"))
      (node (ref "R32") (pin "1") (pinfunction "1_1") (pintype "passive"))
      (node (ref "R34") (pin "1") (pinfunction "1_1") (pintype "passive"))
      (node (ref "R35") (pin "1") (pinfunction "1_1") (pintype "passive"))
      (node (ref "R36") (pin "1") (pinfunction "1_1") (pintype "passive"))
      (node (ref "R38") (pin "1") (pinfunction "1_1") (pintype "passive"))
      (node (ref "R39") (pin "1") (pinfunction "1_1") (pintype "passive"))
      (node (ref "R4") (pin "1") (pinfunction "1_1") (pintype "passive"))
      (node (ref "R40") (pin "1") (pinfunction "1_1") (pintype "passive"))
      (node (ref "R42") (pin "1") (pinfunction "1_1") (pintype "passive"))
      (node (ref "R43") (pin "1") (pinfunction "1_1") (pintype "passive"))
      (node (ref "R44") (pin "1") (pinfunction "1_1") (pintype "passive"))
      (node (ref "R46") (pin "1") (pinfunction "1_1") (pintype "passive"))
      (node (ref "R47") (pin "1") (pinfunction "1_1") (pintype "passive"))
      (node (ref "R48") (pin "1") (pinfunction "1_1") (pintype "passive"))
      (node (ref "R50") (pin "1") (pinfunction "1_1") (pintype "passive"))
      (node (ref "R51") (pin "1") (pinfunction "1_1") (pintype "passive"))
      (node (ref "R52") (pin "1") (pinfunction "1_1") (pintype "passive"))
      (node (ref "R54") (pin "1") (pinfunction "1_1") (pintype "passive"))
      (node (ref "R55") (pin "1") (pinfunction "1_1") (pintype "passive"))
      (node (ref "R56") (pin "1") (pinfunction "1_1") (pintype "passive"))
      (node (ref "R58") (pin "1") (pinfunction "1_1") (pintype "passive"))
      (node (ref "R59") (pin "1") (pinfunction "1_1") (pintype "passive"))
      (node (ref "R6") (pin "1") (pinfunction "1_1") (pintype "passive"))
      (node (ref "R60") (pin "1") (pinfunction "1_1") (pintype "passive"))
      (node (ref "R62") (pin "1") (pinfunction "1_1") (pintype "passive"))
      (node (ref "R63") (pin "1") (pinfunction "1_1") (pintype "passive"))
      (node (ref "R64") (pin "1") (pinfunction "1_1") (pintype "passive"))
      (node (ref "R7") (pin "1") (pinfunction "1_1") (pintype "passive"))
      (node (ref "R8") (pin "1") (pinfunction "1_1") (pintype "passive"))
    )
    (net (code "67") (name "unconnected-(R1-Pad2)") (class "Default")
      (node (ref "R1") (pin "2") (pinfunction "2_2") (pintype "passive"))
    )
    (net (code "68") (name "unconnected-(R5-Pad2)") (class "Default")
      (node (ref "R5") (pin "2") (pinfunction "2_2") (pintype "passive"))
    )
    (net (code "69") (name "unconnected-(R9-Pad2)") (class "Default")
      (node (ref "R9") (pin "2") (pinfunction "2_2") (pintype "passive"))
    )
    (net (code "70") (name "unconnected-(R13-Pad2)") (class "Default")
      (node (ref "R13") (pin "2") (pinfunction "2_2") (pintype "passive"))
    )
    (net (code "71") (name "unconnected-(R17-Pad2)") (class "Default")
      (node (ref "R17") (pin "2") (pinfunction "2_2") (pintype "passive"))
    )
    (net (code "72") (name "unconnected-(R21-Pad2)") (class "Default")
      (node (ref "R21") (pin "2") (pinfunction "2_2") (pintype "passive"))
    )
    (net (code "73") (name "unconnected-(R25-Pad2)") (class "Default")
      (node (ref "R25") (pin "2") (pinfunction "2_2") (pintype "passive"))
    )
    (net (code "74") (name "unconnected-(R29-Pad2)") (class "Default")
      (node (ref "R29") (pin "2") (pinfunction "2_2") (pintype "passive"))
    )
    (net (code "75") (name "unconnected-(R33-Pad2)") (class "Default")
      (node (ref "R33") (pin "2") (pinfunction "2_2") (pintype "passive"))
    )
    (net (code "76") (name "unconnected-(R37-Pad2)") (class "Default")
      (node (ref "R37") (pin "2") (pinfunction "2_2") (pintype "passive"))
    )
    (net (code "77") (name "unconnected-(R41-Pad2)") (class "Default")
      (node (ref "R41") (pin "2") (pinfunction "2_2") (pintype "passive"))
    )
    (net (code "78") (name "unconnected-(R45-Pad2)") (class "Default")
      (node (ref "R45") (pin "2") (pinfunction "2_2") (pintype "passive"))
    )
    (net (code "79") (name "unconnected-(R49-Pad2)") (class "Default")
      (node (ref "R49") (pin "2") (pinfunction "2_2") (pintype "passive"))
    )
    (net (code "80") (name "unconnected-(R53-Pad2)") (class "Default")
      (node (ref "R53") (pin "2") (pinfunction "2_2") (pintype "passive"))
    )
    (net (code "81") (name "unconnected-(R57-Pad2)") (class "Default")
      (node (ref "R57") (pin "2") (pinfunction "2_2") (pintype "passive"))
    )
    (net (code "82") (name "unconnected-(R61-Pad2)") (class "Default")
      (node (ref "R61") (pin "2") (pinfunction "2_2") (pintype "passive"))
    )
    (net (code "83") (name "unconnected-(SLOT1_1-Pad1)") (class "Default")
      (node (ref "SLOT1_1") (pin "1") (pinfunction "1_1") (pintype "passive"))
    )
    (net (code "84") (name "unconnected-(SLOT1_2-Pad1)") (class "Default")
      (node (ref "SLOT1_2") (pin "1") (pinfunction "1_1") (pintype "passive"))
    )
    (net (code "85") (name "unconnected-(SLOT1_3-Pad1)") (class "Default")
      (node (ref "SLOT1_3") (pin "1") (pinfunction "1_1") (pintype "passive"))
    )
    (net (code "86") (name "unconnected-(SLOT2_1-Pad1)") (class "Default")
      (node (ref "SLOT2_1") (pin "1") (pinfunction "1_1") (pintype "passive"))
    )
    (net (code "87") (name "unconnected-(SLOT2_2-Pad1)") (class "Default")
      (node (ref "SLOT2_2") (pin "1") (pinfunction "1_1") (pintype "passive"))
    )
    (net (code "88") (name "unconnected-(SLOT2_3-Pad1)") (class "Default")
      (node (ref "SLOT2_3") (pin "1") (pinfunction "1_1") (pintype "passive"))
    )
    (net (code "89") (name "unconnected-(SLOT3_1-Pad1)") (class "Default")
      (node (ref "SLOT3_1") (pin "1") (pinfunction "1_1") (pintype "passive"))
    )
    (net (code "90") (name "unconnected-(SLOT3_2-Pad1)") (class "Default")
      (node (ref "SLOT3_2") (pin "1") (pinfunction "1_1") (pintype "passive"))
    )
    (net (code "91") (name "unconnected-(SLOT3_3-Pad1)") (class "Default")
      (node (ref "SLOT3_3") (pin "1") (pinfunction "1_1") (pintype "passive"))
    )
    (net (code "92") (name "unconnected-(SLOT4_1-Pad1)") (class "Default")
      (node (ref "SLOT4_1") (pin "1") (pinfunction "1_1") (pintype "passive"))
    )
    (net (code "93") (name "unconnected-(SLOT4_2-Pad1)") (class "Default")
      (node (ref "SLOT4_2") (pin "1") (pinfunction "1_1") (pintype "passive"))
    )
    (net (code "94") (name "unconnected-(SLOT4_3-Pad1)") (class "Default")
      (node (ref "SLOT4_3") (pin "1") (pinfunction "1_1") (pintype "passive"))
    )
    (net (code "95") (name "unconnected-(SLOT5_1-Pad1)") (class "Default")
      (node (ref "SLOT5_1") (pin "1") (pinfunction "1_1") (pintype "passive"))
    )
    (net (code "96") (name "unconnected-(SLOT5_2-Pad1)") (class "Default")
      (node (ref "SLOT5_2") (pin "1") (pinfunction "1_1") (pintype "passive"))
    )
    (net (code "97") (name "unconnected-(SLOT5_3-Pad1)") (class "Default")
      (node (ref "SLOT5_3") (pin "1") (pinfunction "1_1") (pintype "passive"))
    )
    (net (code "98") (name "unconnected-(SLOT6_1-Pad1)") (class "Default")
      (node (ref "SLOT6_1") (pin "1") (pinfunction "1_1") (pintype "passive"))
    )
    (net (code "99") (name "unconnected-(SLOT6_2-Pad1)") (class "Default")
      (node (ref "SLOT6_2") (pin "1") (pinfunction "1_1") (pintype "passive"))
    )
    (net (code "100") (name "unconnected-(SLOT6_3-Pad1)") (class "Default")
      (node (ref "SLOT6_3") (pin "1") (pinfunction "1_1") (pintype "passive"))
    )
    (net (code "101") (name "unconnected-(SLOT7_1-Pad1)") (class "Default")
      (node (ref "SLOT7_1") (pin "1") (pinfunction "1_1") (pintype "passive"))
    )
    (net (code "102") (name "unconnected-(SLOT7_2-Pad1)") (class "Default")
      (node (ref "SLOT7_2") (pin "1") (pinfunction "1_1") (pintype "passive"))
    )
    (net (code "103") (name "unconnected-(SLOT7_3-Pad1)") (class "Default")
      (node (ref "SLOT7_3") (pin "1") (pinfunction "1_1") (pintype "passive"))
    )
    (net (code "104") (name "unconnected-(SLOT8_1-Pad1)") (class "Default")
      (node (ref "SLOT8_1") (pin "1") (pinfunction "1_1") (pintype "passive"))
    )
    (net (code "105") (name "unconnected-(SLOT8_2-Pad1)") (class "Default")
      (node (ref "SLOT8_2") (pin "1") (pinfunction "1_1") (pintype "passive"))
    )
    (net (code "106") (name "unconnected-(SLOT8_3-Pad1)") (class "Default")
      (node (ref "SLOT8_3") (pin "1") (pinfunction "1_1") (pintype "passive"))
    )
    (net (code "107") (name "unconnected-(SLOT9_1-Pad1)") (class "Default")
      (node (ref "SLOT9_1") (pin "1") (pinfunction "1_1") (pintype "passive"))
    )
    (net (code "108") (name "unconnected-(SLOT9_2-Pad1)") (class "Default")
      (node (ref "SLOT9_2") (pin "1") (pinfunction "1_1") (pintype "passive"))
    )
    (net (code "109") (name "unconnected-(SLOT9_3-Pad1)") (class "Default")
      (node (ref "SLOT9_3") (pin "1") (pinfunction "1_1") (pintype "passive"))
    )
    (net (code "110") (name "unconnected-(SLOT10_1-Pad1)") (class "Default")
      (node (ref "SLOT10_1") (pin "1") (pinfunction "1_1") (pintype "passive"))
    )
    (net (code "111") (name "unconnected-(SLOT10_2-Pad1)") (class "Default")
      (node (ref "SLOT10_2") (pin "1") (pinfunction "1_1") (pintype "passive"))
    )
    (net (code "112") (name "unconnected-(SLOT10_3-Pad1)") (class "Default")
      (node (ref "SLOT10_3") (pin "1") (pinfunction "1_1") (pintype "passive"))
    )
    (net (code "113") (name "unconnected-(SLOT11_1-Pad1)") (class "Default")
      (node (ref "SLOT11_1") (pin "1") (pinfunction "1_1") (pintype "passive"))
    )
    (net (code "114") (name "unconnected-(SLOT11_2-Pad1)") (class "Default")
      (node (ref "SLOT11_2") (pin "1") (pinfunction "1_1") (pintype "passive"))
    )
    (net (code "115") (name "unconnected-(SLOT11_3-Pad1)") (class "Default")
      (node (ref "SLOT11_3") (pin "1") (pinfunction "1_1") (pintype "passive"))
    )
    (net (code "116") (name "unconnected-(SLOT12_1-Pad1)") (class "Default")
      (node (ref "SLOT12_1") (pin "1") (pinfunction "1_1") (pintype "passive"))
    )
    (net (code "117") (name "unconnected-(SLOT12_2-Pad1)") (class "Default")
      (node (ref "SLOT12_2") (pin "1") (pinfunction "1_1") (pintype "passive"))
    )
    (net (code "118") (name "unconnected-(SLOT12_3-Pad1)") (class "Default")
      (node (ref "SLOT12_3") (pin "1") (pinfunction "1_1") (pintype "passive"))
    )
    (net (code "119") (name "unconnected-(SLOT13_1-Pad1)") (class "Default")
      (node (ref "SLOT13_1") (pin "1") (pinfunction "1_1") (pintype "passive"))
    )
    (net (code "120") (name "unconnected-(SLOT13_2-Pad1)") (class "Default")
      (node (ref "SLOT13_2") (pin "1") (pinfunction "1_1") (pintype "passive"))
    )
    (net (code "121") (name "unconnected-(SLOT13_4-Pad1)") (class "Default")
      (node (ref "SLOT13_4") (pin "1") (pinfunction "1_1") (pintype "passive"))
    )
    (net (code "122") (name "unconnected-(SLOT14_1-Pad1)") (class "Default")
      (node (ref "SLOT14_1") (pin "1") (pinfunction "1_1") (pintype "passive"))
    )
    (net (code "123") (name "unconnected-(SLOT14_2-Pad1)") (class "Default")
      (node (ref "SLOT14_2") (pin "1") (pinfunction "1_1") (pintype "passive"))
    )
    (net (code "124") (name "unconnected-(SLOT14_3-Pad1)") (class "Default")
      (node (ref "SLOT14_3") (pin "1") (pinfunction "1_1") (pintype "passive"))
    )
    (net (code "125") (name "unconnected-(SLOT15_1-Pad1)") (class "Default")
      (node (ref "SLOT15_1") (pin "1") (pinfunction "1_1") (pintype "passive"))
    )
    (net (code "126") (name "unconnected-(SLOT15_2-Pad1)") (class "Default")
      (node (ref "SLOT15_2") (pin "1") (pinfunction "1_1") (pintype "passive"))
    )
    (net (code "127") (name "unconnected-(SLOT15_3-Pad1)") (class "Default")
      (node (ref "SLOT15_3") (pin "1") (pinfunction "1_1") (pintype "passive"))
    )
    (net (code "128") (name "unconnected-(SLOT16_1-Pad1)") (class "Default")
      (node (ref "SLOT16_1") (pin "1") (pinfunction "1_1") (pintype "passive"))
    )
    (net (code "129") (name "unconnected-(SLOT16_2-Pad1)") (class "Default")
      (node (ref "SLOT16_2") (pin "1") (pinfunction "1_1") (pintype "passive"))
    )
    (net (code "130") (name "unconnected-(SLOT16_3-Pad1)") (class "Default")
      (node (ref "SLOT16_3") (pin "1") (pinfunction "1_1") (pintype "passive"))
    )
  )
)
